# vRef_Therm_Mod_pnl.net
KiCad netlist of a schematic drawn in EAGLE
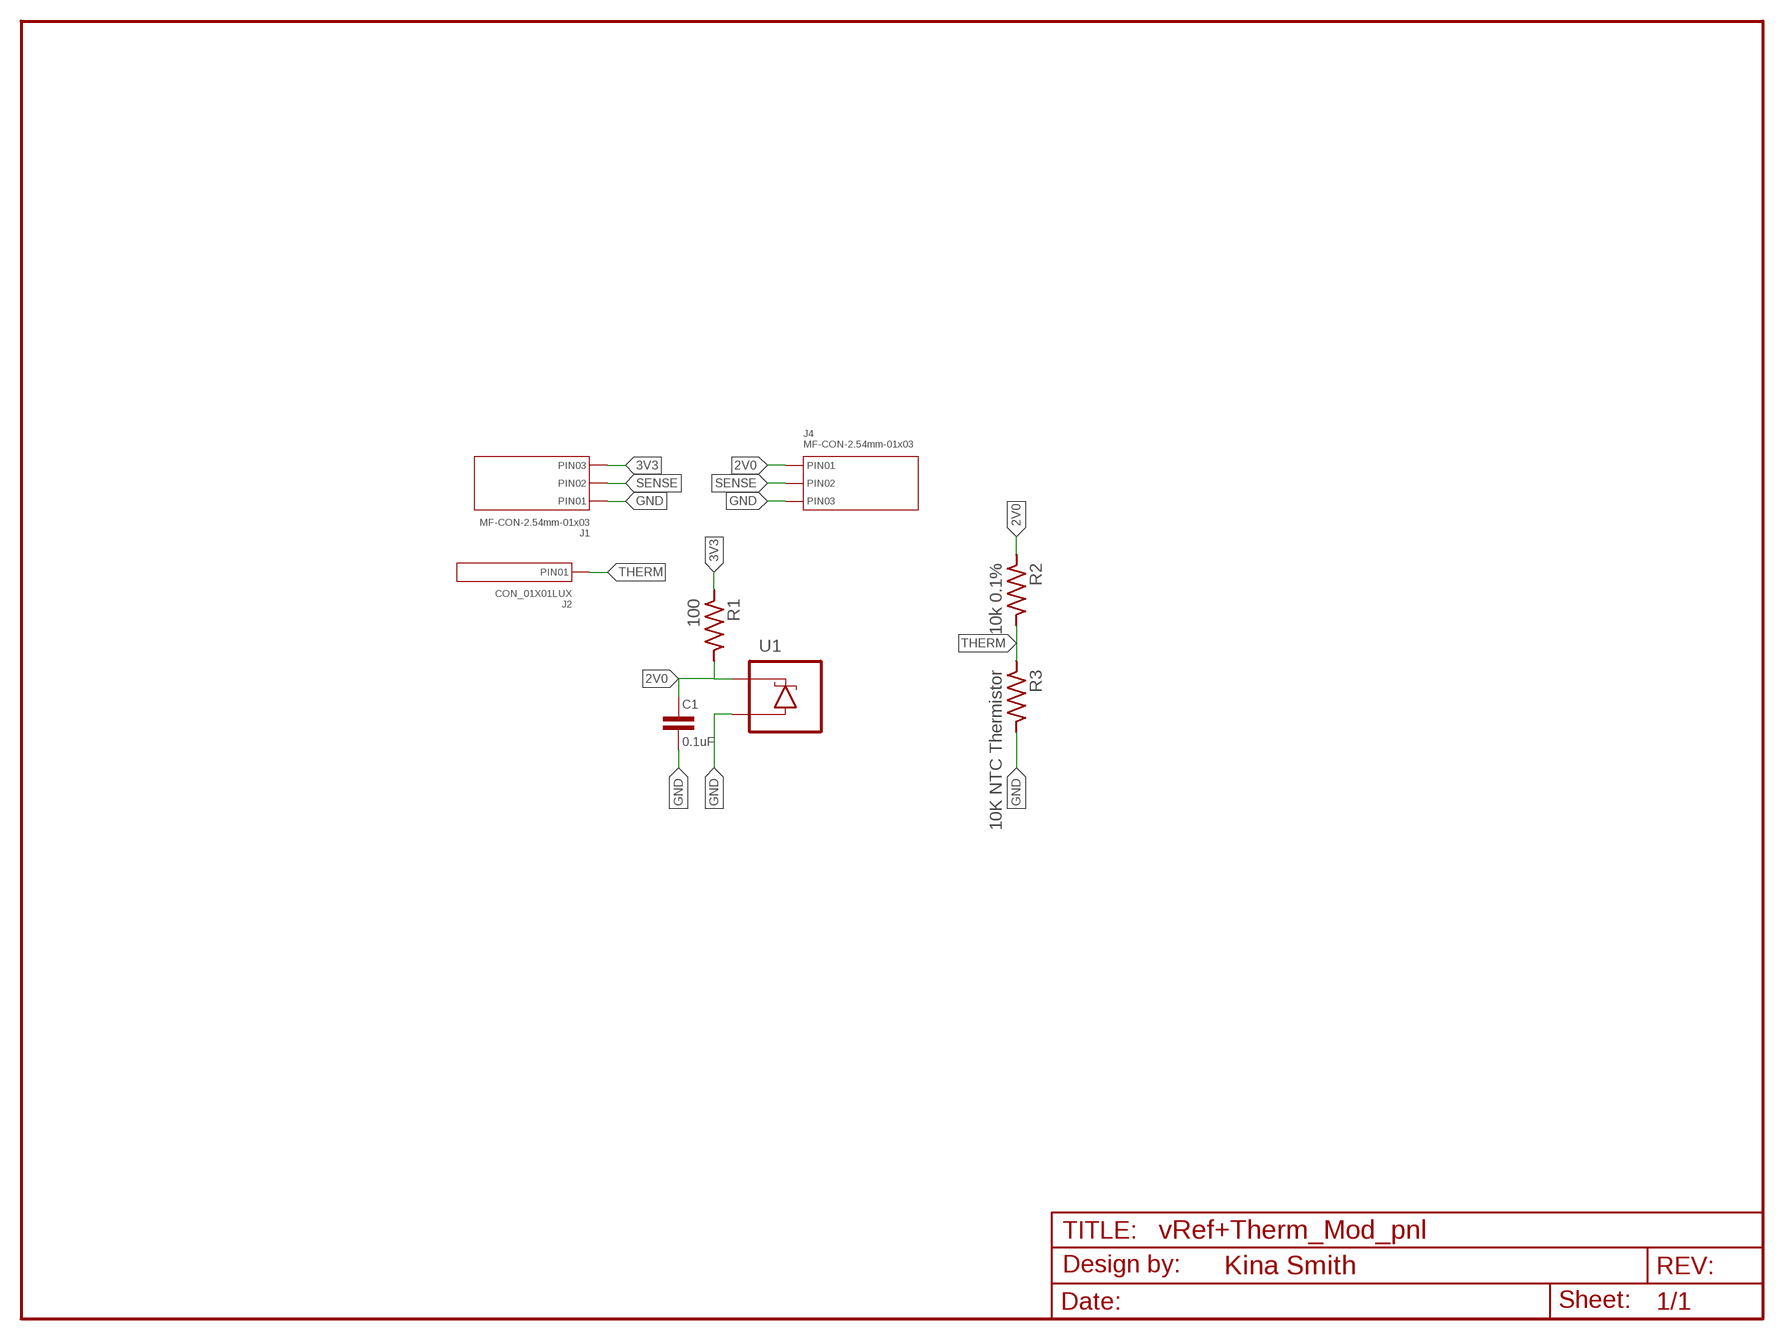
[diagram p0: schematic, sheet 1]

(export (version "E")
  (design (tool "Eeschema 10.0.6"))
  (components
    (comp (ref "C1")
      (value "0.1uF")
      (footprint "eagle-import:C0603-N")
      (libsource (lib "eagle-import") (part "CAPACITOR_NP0603-N"))
    )
    (comp (ref "FRAME1")
      (value "FRAME-LETTERNO_PACKAGE")
      (footprint "eagle-import:DUMMY")
      (fields (field (name "PARTNO") "NA") (field (name "DESIGNER") "Nobody"))
      (libsource (lib "eagle-import") (part "FRAME-LETTERNO_PACKAGE"))
    )
    (comp (ref "J1")
      (value "MF-CON-2.54mm-01x03")
      (footprint "eagle-import:PTH_2.54MM_01X03")
      (fields (field (name "HOUSEPART") "YES"))
      (libsource (lib "eagle-import") (part "CON_01X03_PTH_2.54MM"))
    )
    (comp (ref "J2")
      (value "CON_01X01LUX")
      (footprint "eagle-import:1X01_LUXEON-PAD")
      (libsource (lib "eagle-import") (part "CON_01X01LUX"))
    )
    (comp (ref "J4")
      (value "MF-CON-2.54mm-01x03")
      (footprint "eagle-import:PTH_2.54MM_01X03")
      (fields (field (name "HOUSEPART") "YES"))
      (libsource (lib "eagle-import") (part "CON_01X03_PTH_2.54MM"))
    )
    (comp (ref "R1")
      (value "100")
      (footprint "eagle-import:R0603-N")
      (libsource (lib "eagle-import") (part "RESISTOR0603-N"))
    )
    (comp (ref "R2")
      (value "10k 0.1%")
      (footprint "eagle-import:R0603-N")
      (libsource (lib "eagle-import") (part "RESISTOR0603-N"))
    )
    (comp (ref "R3")
      (value "10K NTC Thermistor")
      (footprint "eagle-import:R0603-N")
      (libsource (lib "eagle-import") (part "RESISTOR0603-N"))
    )
    (comp (ref "U1")
      (value "LM4040-SOT-23-3")
      (footprint "eagle-import:SOT23-3")
      (fields (field (name "PARTNO") "LM4040AIM3-2.0/NOPB "))
      (libsource (lib "eagle-import") (part "LM4040-SOT-23-3"))
    )
  )
  (nets
    (net (code "1") (name "2V0") (class "Default")
      (node (ref "C1") (pin "1") (pinfunction "1_1") (pintype "passive"))
      (node (ref "J4") (pin "P$1") (pinfunction "PIN1_P$1") (pintype "bidirectional"))
      (node (ref "R1") (pin "2") (pinfunction "P$2_2") (pintype "passive"))
      (node (ref "R2") (pin "1") (pinfunction "P$1_1") (pintype "passive"))
      (node (ref "U1") (pin "1") (pinfunction "C_1") (pintype "bidirectional"))
    )
    (net (code "2") (name "3V3") (class "Default")
      (node (ref "J1") (pin "P$3") (pinfunction "PIN3_P$3") (pintype "bidirectional"))
      (node (ref "R1") (pin "1") (pinfunction "P$1_1") (pintype "passive"))
    )
    (net (code "3") (name "GND") (class "Default")
      (node (ref "C1") (pin "2") (pinfunction "2_2") (pintype "passive"))
      (node (ref "J1") (pin "P$1") (pinfunction "PIN1_P$1") (pintype "bidirectional"))
      (node (ref "J4") (pin "P$3") (pinfunction "PIN3_P$3") (pintype "bidirectional"))
      (node (ref "R3") (pin "2") (pinfunction "P$2_2") (pintype "passive"))
      (node (ref "U1") (pin "2") (pinfunction "A_2") (pintype "bidirectional"))
    )
    (net (code "4") (name "SENSE") (class "Default")
      (node (ref "J1") (pin "P$2") (pinfunction "PIN2_P$2") (pintype "bidirectional"))
      (node (ref "J4") (pin "P$2") (pinfunction "PIN2_P$2") (pintype "bidirectional"))
    )
    (net (code "5") (name "THERM") (class "Default")
      (node (ref "J2") (pin "P$1") (pinfunction "PIN1_P$1") (pintype "bidirectional"))
      (node (ref "R2") (pin "2") (pinfunction "P$2_2") (pintype "passive"))
      (node (ref "R3") (pin "1") (pinfunction "P$1_1") (pintype "passive"))
    )
  )
)
